# OTG_Splitter.net
KiCad netlist of a schematic drawn in EAGLE
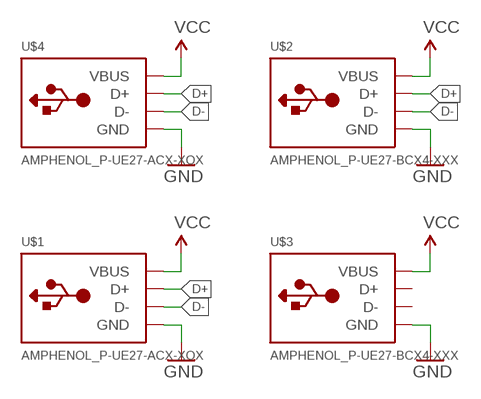
[diagram p0: schematic, sheet 1]

(export (version "E")
  (design (tool "Eeschema 10.0.6"))
  (components
    (comp (ref "U$1")
      (value "AMPHENOL_P-UE27-ACX-XOX")
      (footprint "eagle-import:USBA_AMPHENOL-UE27-RA")
      (libsource (lib "eagle-import") (part "AMPHENOL_P-UE27-ACX-XOX"))
    )
    (comp (ref "U$2")
      (value "AMPHENOL_P-UE27-BCX4-XXX")
      (footprint "eagle-import:USBB_AMPHENOL-UE27-BC")
      (libsource (lib "eagle-import") (part "AMPHENOL_P-UE27-BCX4-XXX"))
    )
    (comp (ref "U$3")
      (value "AMPHENOL_P-UE27-BCX4-XXX")
      (footprint "eagle-import:USBB_AMPHENOL-UE27-BC")
      (libsource (lib "eagle-import") (part "AMPHENOL_P-UE27-BCX4-XXX"))
    )
    (comp (ref "U$4")
      (value "AMPHENOL_P-UE27-ACX-XOX")
      (footprint "eagle-import:USBA_AMPHENOL-UE27-RA")
      (libsource (lib "eagle-import") (part "AMPHENOL_P-UE27-ACX-XOX"))
    )
  )
  (nets
    (net (code "1") (name "D+") (class "Default")
      (node (ref "U$1") (pin "P$3") (pinfunction "D+_P$3") (pintype "bidirectional"))
      (node (ref "U$2") (pin "P$3") (pinfunction "D+_P$3") (pintype "bidirectional"))
      (node (ref "U$4") (pin "P$3") (pinfunction "D+_P$3") (pintype "bidirectional"))
    )
    (net (code "2") (name "D-") (class "Default")
      (node (ref "U$1") (pin "P$2") (pinfunction "D-_P$2") (pintype "bidirectional"))
      (node (ref "U$2") (pin "P$2") (pinfunction "D-_P$2") (pintype "bidirectional"))
      (node (ref "U$4") (pin "P$2") (pinfunction "D-_P$2") (pintype "bidirectional"))
    )
    (net (code "3") (name "GND") (class "Default")
      (node (ref "U$1") (pin "P$4") (pinfunction "GND_P$4") (pintype "power_in"))
      (node (ref "U$2") (pin "P$4") (pinfunction "GND_P$4") (pintype "power_in"))
      (node (ref "U$3") (pin "P$4") (pinfunction "GND_P$4") (pintype "power_in"))
      (node (ref "U$4") (pin "P$4") (pinfunction "GND_P$4") (pintype "power_in"))
    )
    (net (code "4") (name "VCC") (class "Default")
      (node (ref "U$1") (pin "P$1") (pinfunction "VBUS_P$1") (pintype "power_in"))
      (node (ref "U$2") (pin "P$1") (pinfunction "VBUS_P$1") (pintype "power_in"))
      (node (ref "U$3") (pin "P$1") (pinfunction "VBUS_P$1") (pintype "power_in"))
      (node (ref "U$4") (pin "P$1") (pinfunction "VBUS_P$1") (pintype "power_in"))
    )
    (net (code "5") (name "unconnected-(U$3-D+-PadP$3)") (class "Default")
      (node (ref "U$3") (pin "P$3") (pinfunction "D+_P$3") (pintype "bidirectional"))
    )
    (net (code "6") (name "unconnected-(U$3-D--PadP$2)") (class "Default")
      (node (ref "U$3") (pin "P$2") (pinfunction "D-_P$2") (pintype "bidirectional"))
    )
  )
)
